# M307B.net
KiCad netlist of a schematic drawn in EAGLE
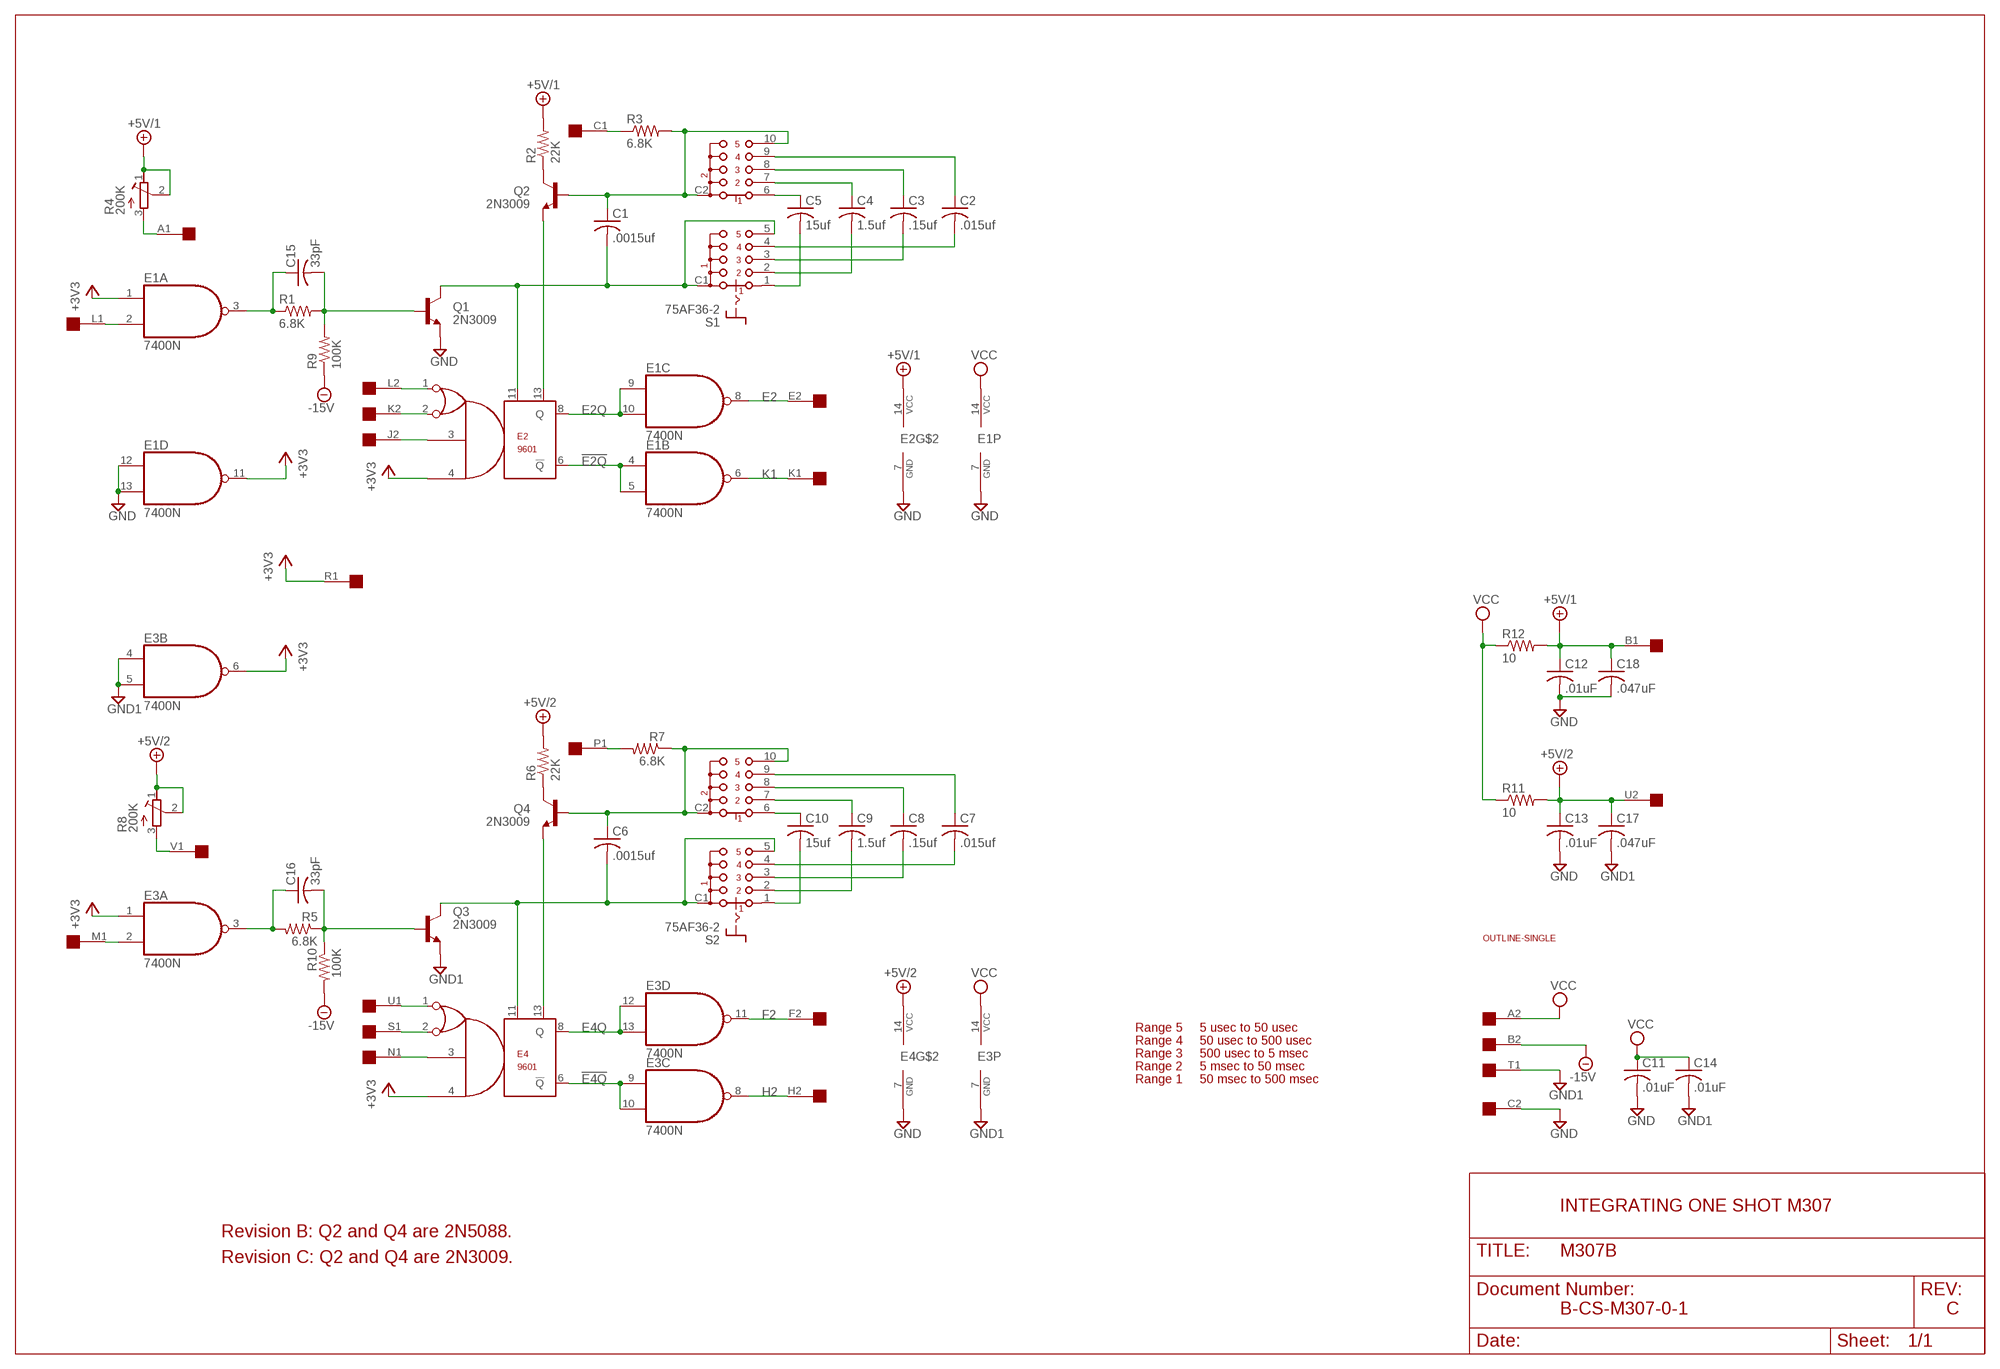
[diagram p0: schematic, sheet 1]

(export (version "E")
  (design (tool "Eeschema 10.0.6"))
  (components
    (comp (ref "C1")
      (value ".0015uf")
      (footprint "eagle-import:C050-025X075")
      (libsource (lib "eagle-import") (part "C-US050-025X075"))
    )
    (comp (ref "C2")
      (value ".015uf")
      (footprint "eagle-import:C150-054X183")
      (libsource (lib "eagle-import") (part "C-US150-054X183"))
    )
    (comp (ref "C3")
      (value ".15uf")
      (footprint "eagle-import:C150-054X183")
      (libsource (lib "eagle-import") (part "C-US150-054X183"))
    )
    (comp (ref "C4")
      (value "1.5uf")
      (footprint "eagle-import:C150-054X183")
      (libsource (lib "eagle-import") (part "C-US150-054X183"))
    )
    (comp (ref "C5")
      (value "15uf")
      (footprint "eagle-import:C150-054X183")
      (libsource (lib "eagle-import") (part "C-US150-054X183"))
    )
    (comp (ref "C6")
      (value ".0015uf")
      (footprint "eagle-import:C050-025X075")
      (libsource (lib "eagle-import") (part "C-US050-025X075"))
    )
    (comp (ref "C7")
      (value ".015uf")
      (footprint "eagle-import:C150-054X183")
      (libsource (lib "eagle-import") (part "C-US150-054X183"))
    )
    (comp (ref "C8")
      (value ".15uf")
      (footprint "eagle-import:C150-054X183")
      (libsource (lib "eagle-import") (part "C-US150-054X183"))
    )
    (comp (ref "C9")
      (value "1.5uf")
      (footprint "eagle-import:C150-054X183")
      (libsource (lib "eagle-import") (part "C-US150-054X183"))
    )
    (comp (ref "C10")
      (value "15uf")
      (footprint "eagle-import:C150-054X183")
      (libsource (lib "eagle-import") (part "C-US150-054X183"))
    )
    (comp (ref "C11")
      (value ".01uF")
      (footprint "eagle-import:C050-025X075")
      (libsource (lib "eagle-import") (part "C-US050-025X075"))
    )
    (comp (ref "C12")
      (value ".01uF")
      (footprint "eagle-import:C050-025X075")
      (libsource (lib "eagle-import") (part "C-US050-025X075"))
    )
    (comp (ref "C13")
      (value ".01uF")
      (footprint "eagle-import:C050-025X075")
      (libsource (lib "eagle-import") (part "C-US050-025X075"))
    )
    (comp (ref "C14")
      (value ".01uF")
      (footprint "eagle-import:C050-025X075")
      (libsource (lib "eagle-import") (part "C-US050-025X075"))
    )
    (comp (ref "C15")
      (value "33pF")
      (footprint "eagle-import:C050-025X075")
      (libsource (lib "eagle-import") (part "C-US050-025X075"))
    )
    (comp (ref "C16")
      (value "33pF")
      (footprint "eagle-import:C050-025X075")
      (libsource (lib "eagle-import") (part "C-US050-025X075"))
    )
    (comp (ref "C17")
      (value ".047uF")
      (footprint "eagle-import:C050-025X075")
      (libsource (lib "eagle-import") (part "C-US050-025X075"))
    )
    (comp (ref "C18")
      (value ".047uF")
      (footprint "eagle-import:C050-025X075")
      (libsource (lib "eagle-import") (part "C-US050-025X075"))
    )
    (comp (ref "E1")
      (value "7400N")
      (footprint "eagle-import:DIL14")
      (libsource (lib "eagle-import") (part "7400N"))
    )
    (comp (ref "E2")
      (value "9601")
      (footprint "eagle-import:DIL14")
      (libsource (lib "eagle-import") (part "9601"))
    )
    (comp (ref "E3")
      (value "7400N")
      (footprint "eagle-import:DIL14")
      (libsource (lib "eagle-import") (part "7400N"))
    )
    (comp (ref "E4")
      (value "9601")
      (footprint "eagle-import:DIL14")
      (libsource (lib "eagle-import") (part "9601"))
    )
    (comp (ref "Q1")
      (value "2N3009")
      (footprint "eagle-import:TO39")
      (libsource (lib "eagle-import") (part "-NPN-TO39-EBC2N3019"))
    )
    (comp (ref "Q2")
      (value "2N3009")
      (footprint "eagle-import:TO39")
      (libsource (lib "eagle-import") (part "-NPN-TO39-EBC2N3019"))
    )
    (comp (ref "Q3")
      (value "2N3009")
      (footprint "eagle-import:TO39")
      (libsource (lib "eagle-import") (part "-NPN-TO39-EBC2N3019"))
    )
    (comp (ref "Q4")
      (value "2N3009")
      (footprint "eagle-import:TO39")
      (libsource (lib "eagle-import") (part "-NPN-TO39-EBC2N3019"))
    )
    (comp (ref "R1")
      (value "6.8K")
      (footprint "eagle-import:0207_10")
      (libsource (lib "eagle-import") (part "R-US_0207/10"))
    )
    (comp (ref "R2")
      (value "22K")
      (footprint "eagle-import:0207_10")
      (libsource (lib "eagle-import") (part "R-US_0207/10"))
    )
    (comp (ref "R3")
      (value "6.8K")
      (footprint "eagle-import:0207_10")
      (libsource (lib "eagle-import") (part "R-US_0207/10"))
    )
    (comp (ref "R4")
      (value "200K")
      (footprint "eagle-import:3006Y")
      (libsource (lib "eagle-import") (part "275P"))
    )
    (comp (ref "R5")
      (value "6.8K")
      (footprint "eagle-import:0207_10")
      (libsource (lib "eagle-import") (part "R-US_0207/10"))
    )
    (comp (ref "R6")
      (value "22K")
      (footprint "eagle-import:0207_10")
      (libsource (lib "eagle-import") (part "R-US_0207/10"))
    )
    (comp (ref "R7")
      (value "6.8K")
      (footprint "eagle-import:0207_10")
      (libsource (lib "eagle-import") (part "R-US_0207/10"))
    )
    (comp (ref "R8")
      (value "200K")
      (footprint "eagle-import:3006Y")
      (libsource (lib "eagle-import") (part "275P"))
    )
    (comp (ref "R9")
      (value "100K")
      (footprint "eagle-import:0207_10")
      (libsource (lib "eagle-import") (part "R-US_0207/10"))
    )
    (comp (ref "R10")
      (value "100K")
      (footprint "eagle-import:0207_10")
      (libsource (lib "eagle-import") (part "R-US_0207/10"))
    )
    (comp (ref "R11")
      (value "10")
      (footprint "eagle-import:0207_10")
      (libsource (lib "eagle-import") (part "R-US_0207/10"))
    )
    (comp (ref "R12")
      (value "10")
      (footprint "eagle-import:0207_10")
      (libsource (lib "eagle-import") (part "R-US_0207/10"))
    )
    (comp (ref "S1")
      (value "75AF36-2")
      (footprint "eagle-import:75AF36-2")
      (libsource (lib "eagle-import") (part "75?36-2AF"))
    )
    (comp (ref "S2")
      (value "75AF36-2")
      (footprint "eagle-import:75AF36-2")
      (libsource (lib "eagle-import") (part "75?36-2AF"))
    )
    (comp (ref "U$1")
      (value "OUTLINE-SINGLE")
      (footprint "eagle-import:SINGLE")
      (libsource (lib "eagle-import") (part "OUTLINE-SINGLE"))
    )
    (comp (ref "U$4")
      (value "SINGLE")
      (footprint "eagle-import:EDGE-CON2")
      (libsource (lib "eagle-import") (part "SINGLE"))
    )
  )
  (nets
    (net (code "1") (name "+3V3") (class "Default")
      (node (ref "E1") (pin "1") (pinfunction "I0_1") (pintype "input"))
      (node (ref "E1") (pin "11") (pinfunction "O_11") (pintype "output"))
      (node (ref "E2") (pin "4") (pinfunction "P$4_4") (pintype "input"))
      (node (ref "E3") (pin "1") (pinfunction "I0_1") (pintype "input"))
      (node (ref "E3") (pin "6") (pinfunction "O_6") (pintype "output"))
      (node (ref "E4") (pin "4") (pinfunction "P$4_4") (pintype "input"))
      (node (ref "U$4") (pin "R1") (pinfunction "1_R1") (pintype "bidirectional"))
    )
    (net (code "2") (name "+5V{slash}1") (class "Default")
      (node (ref "C12") (pin "1") (pinfunction "1_1") (pintype "passive"))
      (node (ref "C18") (pin "1") (pinfunction "1_1") (pintype "passive"))
      (node (ref "E2") (pin "14") (pinfunction "VCC_14") (pintype "power_in"))
      (node (ref "R12") (pin "2") (pinfunction "2_2") (pintype "passive"))
      (node (ref "R2") (pin "2") (pinfunction "2_2") (pintype "passive"))
      (node (ref "R4") (pin "1") (pinfunction "A_1") (pintype "passive"))
      (node (ref "R4") (pin "2") (pinfunction "S_2") (pintype "passive"))
      (node (ref "U$4") (pin "B1") (pinfunction "1_B1") (pintype "bidirectional"))
    )
    (net (code "3") (name "+5V{slash}2") (class "Default")
      (node (ref "C13") (pin "1") (pinfunction "1_1") (pintype "passive"))
      (node (ref "C17") (pin "1") (pinfunction "1_1") (pintype "passive"))
      (node (ref "E4") (pin "14") (pinfunction "VCC_14") (pintype "power_in"))
      (node (ref "R11") (pin "2") (pinfunction "2_2") (pintype "passive"))
      (node (ref "R6") (pin "2") (pinfunction "2_2") (pintype "passive"))
      (node (ref "R8") (pin "1") (pinfunction "A_1") (pintype "passive"))
      (node (ref "R8") (pin "2") (pinfunction "S_2") (pintype "passive"))
      (node (ref "U$4") (pin "U2") (pinfunction "1_U2") (pintype "bidirectional"))
    )
    (net (code "4") (name "-15V") (class "Default")
      (node (ref "R10") (pin "2") (pinfunction "2_2") (pintype "passive"))
      (node (ref "R9") (pin "1") (pinfunction "1_1") (pintype "passive"))
      (node (ref "U$4") (pin "B2") (pinfunction "1_B2") (pintype "bidirectional"))
    )
    (net (code "5") (name "/E2") (class "Default")
      (node (ref "E1") (pin "8") (pinfunction "O_8") (pintype "output"))
      (node (ref "U$4") (pin "E2") (pinfunction "1_E2") (pintype "bidirectional"))
    )
    (net (code "6") (name "/E2Q") (class "Default")
      (node (ref "E1") (pin "10") (pinfunction "I1_10") (pintype "input"))
      (node (ref "E1") (pin "9") (pinfunction "I0_9") (pintype "input"))
      (node (ref "E2") (pin "8") (pinfunction "Q_8") (pintype "output"))
    )
    (net (code "7") (name "/E4Q") (class "Default")
      (node (ref "E3") (pin "12") (pinfunction "I0_12") (pintype "input"))
      (node (ref "E3") (pin "13") (pinfunction "I1_13") (pintype "input"))
      (node (ref "E4") (pin "8") (pinfunction "Q_8") (pintype "output"))
    )
    (net (code "8") (name "/F2") (class "Default")
      (node (ref "E3") (pin "11") (pinfunction "O_11") (pintype "output"))
      (node (ref "U$4") (pin "F2") (pinfunction "1_F2") (pintype "bidirectional"))
    )
    (net (code "9") (name "/H2") (class "Default")
      (node (ref "E3") (pin "8") (pinfunction "O_8") (pintype "output"))
      (node (ref "U$4") (pin "H2") (pinfunction "1_H2") (pintype "bidirectional"))
    )
    (net (code "10") (name "/K1") (class "Default")
      (node (ref "E1") (pin "6") (pinfunction "O_6") (pintype "output"))
      (node (ref "U$4") (pin "K1") (pinfunction "1_K1") (pintype "bidirectional"))
    )
    (net (code "11") (name "/~{E2Q}") (class "Default")
      (node (ref "E1") (pin "4") (pinfunction "I0_4") (pintype "input"))
      (node (ref "E1") (pin "5") (pinfunction "I1_5") (pintype "input"))
      (node (ref "E2") (pin "6") (pinfunction "~{Q}_6") (pintype "output"))
    )
    (net (code "12") (name "/~{E4Q}") (class "Default")
      (node (ref "E3") (pin "10") (pinfunction "I1_10") (pintype "input"))
      (node (ref "E3") (pin "9") (pinfunction "I0_9") (pintype "input"))
      (node (ref "E4") (pin "6") (pinfunction "~{Q}_6") (pintype "output"))
    )
    (net (code "13") (name "GND") (class "Default")
      (node (ref "C11") (pin "2") (pinfunction "2_2") (pintype "passive"))
      (node (ref "C12") (pin "2") (pinfunction "2_2") (pintype "passive"))
      (node (ref "C13") (pin "2") (pinfunction "2_2") (pintype "passive"))
      (node (ref "C18") (pin "2") (pinfunction "2_2") (pintype "passive"))
      (node (ref "E1") (pin "12") (pinfunction "I0_12") (pintype "input"))
      (node (ref "E1") (pin "13") (pinfunction "I1_13") (pintype "input"))
      (node (ref "E1") (pin "7") (pinfunction "GND_7") (pintype "power_in"))
      (node (ref "E2") (pin "7") (pinfunction "GND_7") (pintype "power_in"))
      (node (ref "E4") (pin "7") (pinfunction "GND_7") (pintype "power_in"))
      (node (ref "Q1") (pin "1") (pinfunction "E_1") (pintype "passive"))
      (node (ref "U$4") (pin "C2") (pinfunction "1_C2") (pintype "bidirectional"))
    )
    (net (code "14") (name "GND1") (class "Default")
      (node (ref "C14") (pin "2") (pinfunction "2_2") (pintype "passive"))
      (node (ref "C17") (pin "2") (pinfunction "2_2") (pintype "passive"))
      (node (ref "E3") (pin "4") (pinfunction "I0_4") (pintype "input"))
      (node (ref "E3") (pin "5") (pinfunction "I1_5") (pintype "input"))
      (node (ref "E3") (pin "7") (pinfunction "GND_7") (pintype "power_in"))
      (node (ref "Q3") (pin "1") (pinfunction "E_1") (pintype "passive"))
      (node (ref "U$4") (pin "T1") (pinfunction "1_T1") (pintype "bidirectional"))
    )
    (net (code "15") (name "Net-(E1A-I1)") (class "Default")
      (node (ref "E1") (pin "2") (pinfunction "I1_2") (pintype "input"))
      (node (ref "U$4") (pin "L1") (pinfunction "1_L1") (pintype "bidirectional"))
    )
    (net (code "16") (name "Net-(E1A-O)") (class "Default")
      (node (ref "C15") (pin "1") (pinfunction "1_1") (pintype "passive"))
      (node (ref "E1") (pin "3") (pinfunction "O_3") (pintype "output"))
      (node (ref "R1") (pin "1") (pinfunction "1_1") (pintype "passive"))
    )
    (net (code "17") (name "Net-(E2A-P$1)") (class "Default")
      (node (ref "E2") (pin "1") (pinfunction "P$1_1") (pintype "input"))
      (node (ref "U$4") (pin "L2") (pinfunction "1_L2") (pintype "bidirectional"))
    )
    (net (code "18") (name "Net-(E2A-P$2)") (class "Default")
      (node (ref "E2") (pin "2") (pinfunction "P$2_2") (pintype "input"))
      (node (ref "U$4") (pin "K2") (pinfunction "1_K2") (pintype "bidirectional"))
    )
    (net (code "19") (name "Net-(E2A-P$3)") (class "Default")
      (node (ref "E2") (pin "3") (pinfunction "P$3_3") (pintype "input"))
      (node (ref "U$4") (pin "J2") (pinfunction "1_J2") (pintype "bidirectional"))
    )
    (net (code "20") (name "Net-(E2A-P$5)") (class "Default")
      (node (ref "C1") (pin "2") (pinfunction "2_2") (pintype "passive"))
      (node (ref "E2") (pin "11") (pinfunction "P$5_11") (pintype "bidirectional"))
      (node (ref "Q1") (pin "3") (pinfunction "C_3") (pintype "passive"))
      (node (ref "S1") (pin "5") (pinfunction "51_5") (pintype "passive"))
      (node (ref "S1") (pin "C1") (pinfunction "C1_C1") (pintype "passive"))
    )
    (net (code "21") (name "Net-(E2A-P$6)") (class "Default")
      (node (ref "E2") (pin "13") (pinfunction "P$6_13") (pintype "bidirectional"))
      (node (ref "Q2") (pin "1") (pinfunction "E_1") (pintype "passive"))
    )
    (net (code "22") (name "Net-(E3A-I1)") (class "Default")
      (node (ref "E3") (pin "2") (pinfunction "I1_2") (pintype "input"))
      (node (ref "U$4") (pin "M1") (pinfunction "1_M1") (pintype "bidirectional"))
    )
    (net (code "23") (name "Net-(E3A-O)") (class "Default")
      (node (ref "C16") (pin "1") (pinfunction "1_1") (pintype "passive"))
      (node (ref "E3") (pin "3") (pinfunction "O_3") (pintype "output"))
      (node (ref "R5") (pin "2") (pinfunction "2_2") (pintype "passive"))
    )
    (net (code "24") (name "Net-(E4A-P$1)") (class "Default")
      (node (ref "E4") (pin "1") (pinfunction "P$1_1") (pintype "input"))
      (node (ref "U$4") (pin "U1") (pinfunction "1_U1") (pintype "bidirectional"))
    )
    (net (code "25") (name "Net-(E4A-P$2)") (class "Default")
      (node (ref "E4") (pin "2") (pinfunction "P$2_2") (pintype "input"))
      (node (ref "U$4") (pin "S1") (pinfunction "1_S1") (pintype "bidirectional"))
    )
    (net (code "26") (name "Net-(E4A-P$3)") (class "Default")
      (node (ref "E4") (pin "3") (pinfunction "P$3_3") (pintype "input"))
      (node (ref "U$4") (pin "N1") (pinfunction "1_N1") (pintype "bidirectional"))
    )
    (net (code "27") (name "Net-(E4A-P$5)") (class "Default")
      (node (ref "C6") (pin "2") (pinfunction "2_2") (pintype "passive"))
      (node (ref "E4") (pin "11") (pinfunction "P$5_11") (pintype "bidirectional"))
      (node (ref "Q3") (pin "3") (pinfunction "C_3") (pintype "passive"))
      (node (ref "S2") (pin "5") (pinfunction "51_5") (pintype "passive"))
      (node (ref "S2") (pin "C1") (pinfunction "C1_C1") (pintype "passive"))
    )
    (net (code "28") (name "Net-(E4A-P$6)") (class "Default")
      (node (ref "E4") (pin "13") (pinfunction "P$6_13") (pintype "bidirectional"))
      (node (ref "Q4") (pin "1") (pinfunction "E_1") (pintype "passive"))
    )
    (net (code "29") (name "Net-(Q1-B)") (class "Default")
      (node (ref "C15") (pin "2") (pinfunction "2_2") (pintype "passive"))
      (node (ref "Q1") (pin "2") (pinfunction "B_2") (pintype "passive"))
      (node (ref "R1") (pin "2") (pinfunction "2_2") (pintype "passive"))
      (node (ref "R9") (pin "2") (pinfunction "2_2") (pintype "passive"))
    )
    (net (code "30") (name "Net-(Q2-B)") (class "Default")
      (node (ref "C1") (pin "1") (pinfunction "1_1") (pintype "passive"))
      (node (ref "Q2") (pin "2") (pinfunction "B_2") (pintype "passive"))
      (node (ref "R3") (pin "2") (pinfunction "2_2") (pintype "passive"))
      (node (ref "S1") (pin "10") (pinfunction "52_10") (pintype "passive"))
      (node (ref "S1") (pin "C2") (pinfunction "C2_C2") (pintype "passive"))
    )
    (net (code "31") (name "Net-(Q2-C)") (class "Default")
      (node (ref "Q2") (pin "3") (pinfunction "C_3") (pintype "passive"))
      (node (ref "R2") (pin "1") (pinfunction "1_1") (pintype "passive"))
    )
    (net (code "32") (name "Net-(Q3-B)") (class "Default")
      (node (ref "C16") (pin "2") (pinfunction "2_2") (pintype "passive"))
      (node (ref "Q3") (pin "2") (pinfunction "B_2") (pintype "passive"))
      (node (ref "R10") (pin "1") (pinfunction "1_1") (pintype "passive"))
      (node (ref "R5") (pin "1") (pinfunction "1_1") (pintype "passive"))
    )
    (net (code "33") (name "Net-(Q4-B)") (class "Default")
      (node (ref "C6") (pin "1") (pinfunction "1_1") (pintype "passive"))
      (node (ref "Q4") (pin "2") (pinfunction "B_2") (pintype "passive"))
      (node (ref "R7") (pin "1") (pinfunction "1_1") (pintype "passive"))
      (node (ref "S2") (pin "10") (pinfunction "52_10") (pintype "passive"))
      (node (ref "S2") (pin "C2") (pinfunction "C2_C2") (pintype "passive"))
    )
    (net (code "34") (name "Net-(Q4-C)") (class "Default")
      (node (ref "Q4") (pin "3") (pinfunction "C_3") (pintype "passive"))
      (node (ref "R6") (pin "1") (pinfunction "1_1") (pintype "passive"))
    )
    (net (code "35") (name "Net-(R4-E)") (class "Default")
      (node (ref "R4") (pin "3") (pinfunction "E_3") (pintype "passive"))
      (node (ref "U$4") (pin "A1") (pinfunction "1_A1") (pintype "bidirectional"))
    )
    (net (code "36") (name "Net-(R8-E)") (class "Default")
      (node (ref "R8") (pin "3") (pinfunction "E_3") (pintype "passive"))
      (node (ref "U$4") (pin "V1") (pinfunction "1_V1") (pintype "bidirectional"))
    )
    (net (code "37") (name "Net-(S1-11)") (class "Default")
      (node (ref "C5") (pin "2") (pinfunction "2_2") (pintype "passive"))
      (node (ref "S1") (pin "1") (pinfunction "11_1") (pintype "passive"))
    )
    (net (code "38") (name "Net-(S1-12)") (class "Default")
      (node (ref "C5") (pin "1") (pinfunction "1_1") (pintype "passive"))
      (node (ref "S1") (pin "6") (pinfunction "12_6") (pintype "passive"))
    )
    (net (code "39") (name "Net-(S1-21)") (class "Default")
      (node (ref "C4") (pin "2") (pinfunction "2_2") (pintype "passive"))
      (node (ref "S1") (pin "2") (pinfunction "21_2") (pintype "passive"))
    )
    (net (code "40") (name "Net-(S1-22)") (class "Default")
      (node (ref "C4") (pin "1") (pinfunction "1_1") (pintype "passive"))
      (node (ref "S1") (pin "7") (pinfunction "22_7") (pintype "passive"))
    )
    (net (code "41") (name "Net-(S1-31)") (class "Default")
      (node (ref "C3") (pin "2") (pinfunction "2_2") (pintype "passive"))
      (node (ref "S1") (pin "3") (pinfunction "31_3") (pintype "passive"))
    )
    (net (code "42") (name "Net-(S1-32)") (class "Default")
      (node (ref "C3") (pin "1") (pinfunction "1_1") (pintype "passive"))
      (node (ref "S1") (pin "8") (pinfunction "32_8") (pintype "passive"))
    )
    (net (code "43") (name "Net-(S1-41)") (class "Default")
      (node (ref "C2") (pin "2") (pinfunction "2_2") (pintype "passive"))
      (node (ref "S1") (pin "4") (pinfunction "41_4") (pintype "passive"))
    )
    (net (code "44") (name "Net-(S1-42)") (class "Default")
      (node (ref "C2") (pin "1") (pinfunction "1_1") (pintype "passive"))
      (node (ref "S1") (pin "9") (pinfunction "42_9") (pintype "passive"))
    )
    (net (code "45") (name "Net-(S2-11)") (class "Default")
      (node (ref "C10") (pin "2") (pinfunction "2_2") (pintype "passive"))
      (node (ref "S2") (pin "1") (pinfunction "11_1") (pintype "passive"))
    )
    (net (code "46") (name "Net-(S2-12)") (class "Default")
      (node (ref "C10") (pin "1") (pinfunction "1_1") (pintype "passive"))
      (node (ref "S2") (pin "6") (pinfunction "12_6") (pintype "passive"))
    )
    (net (code "47") (name "Net-(S2-21)") (class "Default")
      (node (ref "C9") (pin "2") (pinfunction "2_2") (pintype "passive"))
      (node (ref "S2") (pin "2") (pinfunction "21_2") (pintype "passive"))
    )
    (net (code "48") (name "Net-(S2-22)") (class "Default")
      (node (ref "C9") (pin "1") (pinfunction "1_1") (pintype "passive"))
      (node (ref "S2") (pin "7") (pinfunction "22_7") (pintype "passive"))
    )
    (net (code "49") (name "Net-(S2-31)") (class "Default")
      (node (ref "C8") (pin "2") (pinfunction "2_2") (pintype "passive"))
      (node (ref "S2") (pin "3") (pinfunction "31_3") (pintype "passive"))
    )
    (net (code "50") (name "Net-(S2-32)") (class "Default")
      (node (ref "C8") (pin "1") (pinfunction "1_1") (pintype "passive"))
      (node (ref "S2") (pin "8") (pinfunction "32_8") (pintype "passive"))
    )
    (net (code "51") (name "Net-(S2-41)") (class "Default")
      (node (ref "C7") (pin "2") (pinfunction "2_2") (pintype "passive"))
      (node (ref "S2") (pin "4") (pinfunction "41_4") (pintype "passive"))
    )
    (net (code "52") (name "Net-(S2-42)") (class "Default")
      (node (ref "C7") (pin "1") (pinfunction "1_1") (pintype "passive"))
      (node (ref "S2") (pin "9") (pinfunction "42_9") (pintype "passive"))
    )
    (net (code "53") (name "Net-(U$4E-1)") (class "Default")
      (node (ref "R3") (pin "1") (pinfunction "1_1") (pintype "passive"))
      (node (ref "U$4") (pin "C1") (pinfunction "1_C1") (pintype "bidirectional"))
    )
    (net (code "54") (name "Net-(U$4Y-1)") (class "Default")
      (node (ref "R7") (pin "2") (pinfunction "2_2") (pintype "passive"))
      (node (ref "U$4") (pin "P1") (pinfunction "1_P1") (pintype "bidirectional"))
    )
    (net (code "55") (name "VCC") (class "Default")
      (node (ref "C11") (pin "1") (pinfunction "1_1") (pintype "passive"))
      (node (ref "C14") (pin "1") (pinfunction "1_1") (pintype "passive"))
      (node (ref "E1") (pin "14") (pinfunction "VCC_14") (pintype "power_in"))
      (node (ref "E3") (pin "14") (pinfunction "VCC_14") (pintype "power_in"))
      (node (ref "R11") (pin "1") (pinfunction "1_1") (pintype "passive"))
      (node (ref "R12") (pin "1") (pinfunction "1_1") (pintype "passive"))
      (node (ref "U$4") (pin "A2") (pinfunction "1_A2") (pintype "bidirectional"))
    )
  )
)
